# FPGA_SPI_interface.net
KiCad netlist of a schematic drawn in Altium Designer
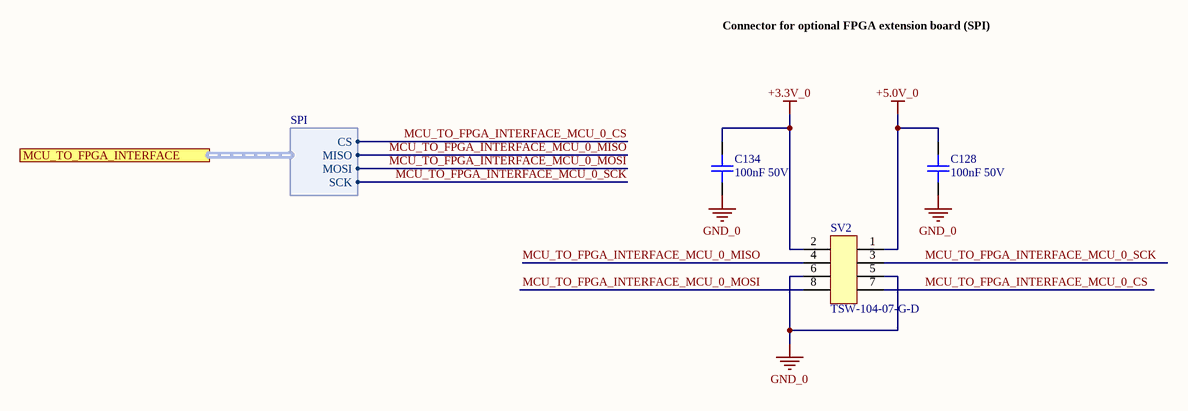
[diagram p0: FPGA_SPI_interface.SchDoc]

(export (version "E")
  (design (tool "Eeschema 10.0.6"))
  (components
    (comp (ref "C128")
      (value "100nF 50V")
      (footprint "0603C")
      (description "Ceramic, 100nF, ±10%, 50V, X7R, –55 to 125°C, 0603 (1608),RoHS, Automotive")
      (fields (field (name "PART NUMBER") "GCJ188R71H104KA12") (field (name "TOLERANCE") "±10%"))
      (libsource (lib "master-010106") (part "C"))
    )
    (comp (ref "C134")
      (value "100nF 50V")
      (footprint "0603C")
      (description "Ceramic, 100nF, ±10%, 50V, X7R, –55 to 125°C, 0603 (1608),RoHS, Automotive")
      (fields (field (name "PART NUMBER") "GCJ188R71H104KA12") (field (name "TOLERANCE") "±10%"))
      (libsource (lib "master-010106") (part "C"))
    )
    (comp (ref "SV2")
      (value "TSW-104-07-G-D")
      (footprint "Pinheader_2.54_2x4")
      (description "Board-To-Board Connector, Vertical, 2.54 mm, 8 Contacts, Header, TSW Series, Through Hole, 2 Rows")
      (fields (field (name "MANUFACTURER") "Samtec"))
      (libsource (lib "OE750") (part "X2x4"))
    )
  )
  (nets
    (net (code "2") (name "+3.3V_0") (class "Default")
      (node (ref "C134") (pin "2") (pinfunction "2_2") (pintype "passive"))
      (node (ref "SV2") (pin "2") (pintype "passive"))
    )
    (net (code "3") (name "+5.0V_0") (class "Default")
      (node (ref "C128") (pin "1") (pinfunction "1_1") (pintype "passive"))
      (node (ref "SV2") (pin "1") (pintype "passive"))
    )
    (net (code "4") (name "/MCU_TO_FPGA_INTERFACE_MCU_0_CS") (class "Default")
      (node (ref "SV2") (pin "7") (pintype "passive"))
    )
    (net (code "5") (name "/MCU_TO_FPGA_INTERFACE_MCU_0_MISO") (class "Default")
      (node (ref "SV2") (pin "4") (pintype "passive"))
    )
    (net (code "6") (name "/MCU_TO_FPGA_INTERFACE_MCU_0_MOSI") (class "Default")
      (node (ref "SV2") (pin "8") (pintype "passive"))
    )
    (net (code "7") (name "/MCU_TO_FPGA_INTERFACE_MCU_0_SCK") (class "Default")
      (node (ref "SV2") (pin "3") (pintype "passive"))
    )
    (net (code "9") (name "GND_0") (class "Default")
      (node (ref "C128") (pin "2") (pinfunction "2_2") (pintype "passive"))
      (node (ref "C134") (pin "1") (pinfunction "1_1") (pintype "passive"))
      (node (ref "SV2") (pin "5") (pintype "passive"))
      (node (ref "SV2") (pin "6") (pintype "passive"))
    )
  )
)
